# iotaCore-Power.net
KiCad netlist of a schematic drawn in Altium Designer
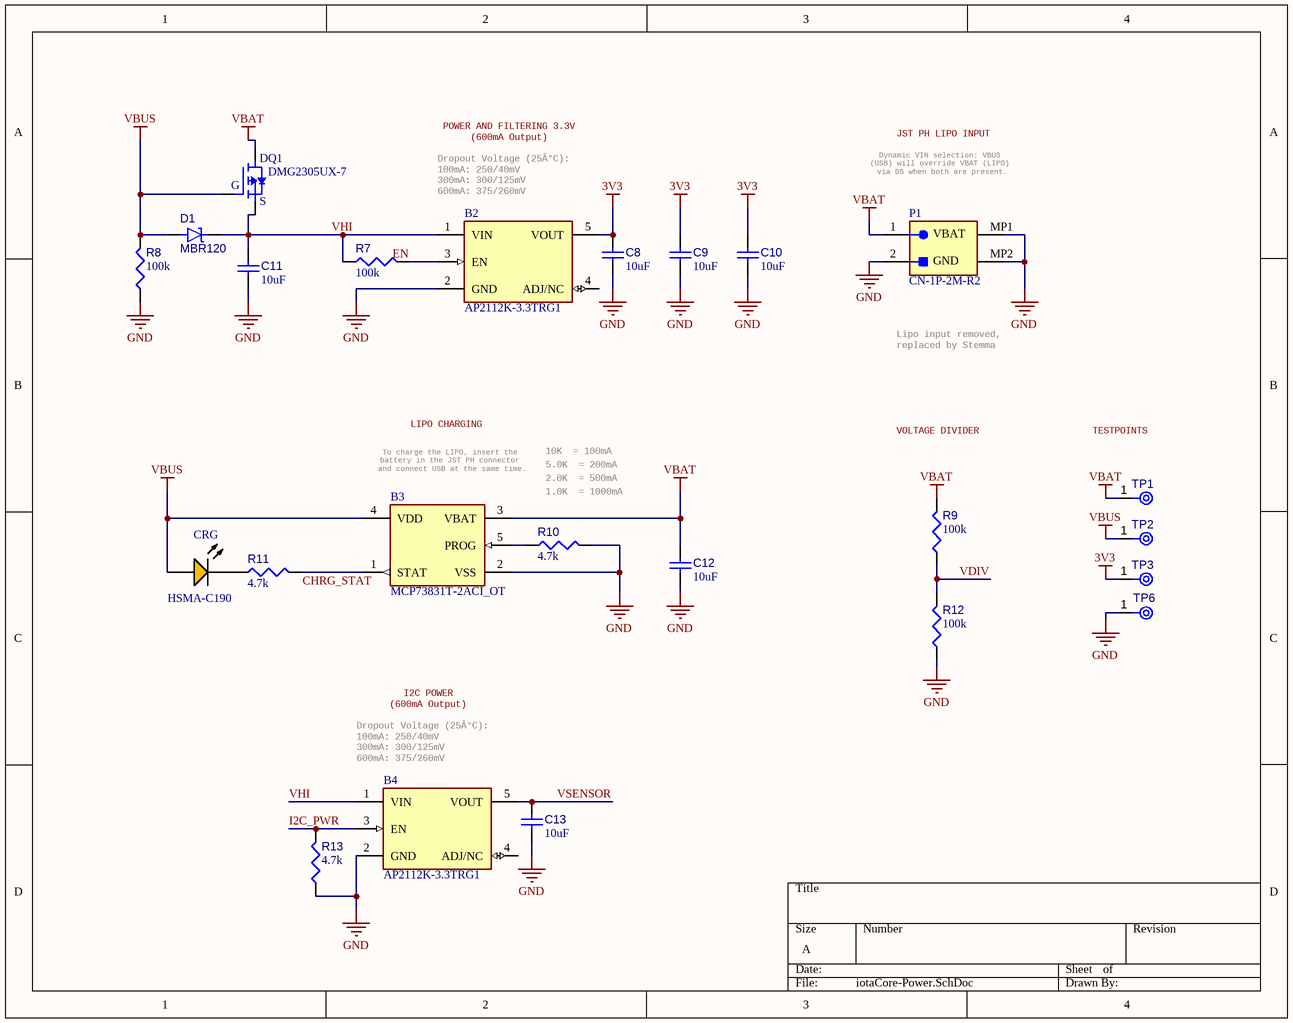
[diagram p0: iotaCore-Power.SchDoc]

(export (version "E")
  (design (tool "Eeschema 10.0.6"))
  (components
    (comp (ref "B2")
      (value "AP2112K-3.3TRG1")
      (footprint "SOT95P270X145-5N")
      (fields (field (name "MOUSER PART NUMBER") "621-AP2112K-3.3TRG1"))
      (libsource (lib "Prototypical Design") (part "AP2112K-3.3TRG1"))
    )
    (comp (ref "B3")
      (value "MCP73831T-2ACI_OT")
      (footprint "SOT95P270X145-5N")
      (description "Li-Ion Charge Controller 4.2V SOT23-5")
      (fields
        (field (name "MOUSER PART NUMBER") "579-MCP73831T-2ACIOT")
        (field (name "MANUFACTURER_PART_NUMBER") "MCP73831T-2ACI/OT")
      )
      (libsource (lib "Prototypical Design") (part "MCP73831T-2ACI_OT"))
    )
    (comp (ref "B4")
      (value "AP2112K-3.3TRG1")
      (footprint "SOT95P270X145-5N")
      (fields (field (name "MOUSER PART NUMBER") "621-AP2112K-3.3TRG1"))
      (libsource (lib "Prototypical Design") (part "AP2112K-3.3TRG1"))
    )
    (comp (ref "C8")
      (value "10uF")
      (footprint "CAPC1608X87X35NL15T15")
      (description "Chip Capacitor, 10 uF, +/- 0.25 uF, 50 V, 0603 (1608 Metric)")
      (fields
        (field (name "TOLERANCE") "0.25%")
        (field (name "Comment") "Capacitor 10 uF +/- 0.25 uF 50 V 0603")
      )
      (libsource (lib "Prototypical Design") (part "CAP-NP-2"))
    )
    (comp (ref "C9")
      (value "10uF")
      (footprint "CAPC1608X87X35NL15T15")
      (description "Chip Capacitor, 10 uF, +/- 0.25 uF, 50 V, 0603 (1608 Metric)")
      (fields
        (field (name "TOLERANCE") "0.25%")
        (field (name "Comment") "Capacitor 10 uF +/- 0.25 uF 50 V 0603")
      )
      (libsource (lib "Prototypical Design") (part "CAP-NP-2"))
    )
    (comp (ref "C10")
      (value "10uF")
      (footprint "CAPC1608X87X35NL15T15")
      (description "Chip Capacitor, 10 uF, +/- 0.25 uF, 50 V, 0603 (1608 Metric)")
      (fields
        (field (name "TOLERANCE") "0.25%")
        (field (name "Comment") "Capacitor 10 uF +/- 0.25 uF 50 V 0603")
      )
      (libsource (lib "Prototypical Design") (part "CAP-NP-2"))
    )
    (comp (ref "C11")
      (value "10uF")
      (footprint "CAPC1608X87X35NL15T15")
      (description "Chip Capacitor, 10 uF, +/- 0.25 uF, 50 V, 0603 (1608 Metric)")
      (fields
        (field (name "TOLERANCE") "0.25%")
        (field (name "Comment") "Capacitor 10 uF +/- 0.25 uF 50 V 0603")
      )
      (libsource (lib "Prototypical Design") (part "CAP-NP-2"))
    )
    (comp (ref "C12")
      (value "10uF")
      (footprint "CAPC1608X87X35NL15T15")
      (description "Chip Capacitor, 10 uF, +/- 0.25 uF, 50 V, 0603 (1608 Metric)")
      (fields
        (field (name "TOLERANCE") "0.25%")
        (field (name "Comment") "Capacitor 10 uF +/- 0.25 uF 50 V 0603")
      )
      (libsource (lib "Prototypical Design") (part "CAP-NP-2"))
    )
    (comp (ref "C13")
      (value "10uF")
      (footprint "CAPC1608X87X35NL15T15")
      (description "Chip Capacitor, 10 uF, +/- 0.25 uF, 50 V, 0603 (1608 Metric)")
      (fields
        (field (name "TOLERANCE") "0.25%")
        (field (name "Comment") "Capacitor 10 uF +/- 0.25 uF 50 V 0603")
      )
      (libsource (lib "Prototypical Design") (part "CAP-NP-2"))
    )
    (comp (ref "CRG")
      (value "HSMA-C190")
      (footprint "AVAG-HSMX-C190_V")
      (description "LED Uni-Color Amber, 60 mW, 20 mA, -40 to 85 degC, 2-Pin SMD, RoHS, Tape and Reel")
      (fields (field (name "POWER") "60mW") (field (name "MANUFACTURER") "Avago"))
      (libsource (lib "Prototypical Design") (part "LED-AMBER-AK-2"))
    )
    (comp (ref "D1")
      (value "MBR120")
      (footprint "ONSC-SOD-123FL-2-498-01_V")
      (description "Diode")
      (libsource (lib "Prototypical Design") (part "MBR120"))
    )
    (comp (ref "P1")
      (value "CN-1P-2M-R2")
      (footprint "JST- S2B-PH-SM4-TB(LF)(SN)-2_V")
      (libsource (lib "Prototypical Design") (part "CN-1P-2M-R2"))
    )
    (comp (ref "Q1")
      (value "DMG2305UX-7")
      (footprint "FP-SOT23-MFG")
      (libsource (lib "Prototypical Design") (part "MOSFET-NPN-3"))
    )
    (comp (ref "R7")
      (value "100k")
      (footprint "RESC1608X55X25ML10T15")
      (description "Chip Resistor, 100 KOhm, +/- 1%, 0.1 W, -55 to 155 degC, 0603 (1608 Metric)")
      (fields (field (name "TOLERANCE") "1%") (field (name "POWER") "100mW"))
      (libsource (lib "Prototypical Design") (part "RES-2"))
    )
    (comp (ref "R8")
      (value "100k")
      (footprint "RESC1608X55X25ML10T15")
      (description "Chip Resistor, 100 KOhm, +/- 1%, 0.1 W, -55 to 155 degC, 0603 (1608 Metric)")
      (fields (field (name "TOLERANCE") "1%") (field (name "POWER") "100mW"))
      (libsource (lib "Prototypical Design") (part "RES-2"))
    )
    (comp (ref "R9")
      (value "100k")
      (footprint "RESC1608X55X25ML10T15")
      (description "Chip Resistor, 100 KOhm, +/- 1%, 0.1 W, -55 to 155 degC, 0603 (1608 Metric)")
      (fields (field (name "TOLERANCE") "1%") (field (name "POWER") "100mW"))
      (libsource (lib "Prototypical Design") (part "RES-2"))
    )
    (comp (ref "R10")
      (value "4.7k")
      (footprint "RESC1608X55X25ML10T15")
      (description "Chip Resistor, 4.7 KOhm, +/- 1%, 0.1 W, -55 to 155 degC, 0603 (1608 Metric)")
      (fields (field (name "TOLERANCE") "1%") (field (name "POWER") "100mW"))
      (libsource (lib "Prototypical Design") (part "RES-2"))
    )
    (comp (ref "R11")
      (value "4.7k")
      (footprint "RESC1608X55X25ML10T15")
      (description "Chip Resistor, 1 KOhm, +/- 1%, 0.1 W, -55 to 155 degC, 0603 (1608 Metric)")
      (fields (field (name "TOLERANCE") "1%") (field (name "POWER") "100mW"))
      (libsource (lib "Prototypical Design") (part "RES-2"))
    )
    (comp (ref "R12")
      (value "100k")
      (footprint "RESC1608X55X25ML10T15")
      (description "Chip Resistor, 100 KOhm, +/- 1%, 0.1 W, -55 to 155 degC, 0603 (1608 Metric)")
      (fields (field (name "TOLERANCE") "1%") (field (name "POWER") "100mW"))
      (libsource (lib "Prototypical Design") (part "RES-2"))
    )
    (comp (ref "R13")
      (value "4.7k")
      (footprint "RESC1608X55X25ML10T15")
      (description "Chip Resistor, 4.7 KOhm, +/- 1%, 0.1 W, -55 to 155 degC, 0603 (1608 Metric)")
      (fields (field (name "TOLERANCE") "1%") (field (name "POWER") "100mW"))
      (libsource (lib "Prototypical Design") (part "RES-2"))
    )
    (comp (ref "TP1")
      (value "TPAD6R")
      (footprint "TP06R")
      (description "0.6mm round")
      (libsource (lib "McIntyre Industries") (part "CMP-001-0001-4"))
    )
    (comp (ref "TP2")
      (value "TPAD6R")
      (footprint "TP06R")
      (description "0.6mm round")
      (libsource (lib "McIntyre Industries") (part "CMP-001-0001-4"))
    )
    (comp (ref "TP3")
      (value "TPAD6R")
      (footprint "TP06R")
      (description "0.6mm round")
      (libsource (lib "McIntyre Industries") (part "CMP-001-0001-4"))
    )
    (comp (ref "TP6")
      (value "TPAD6R")
      (footprint "TP06R")
      (description "0.6mm round")
      (libsource (lib "McIntyre Industries") (part "CMP-001-0001-4"))
    )
  )
  (nets
    (net (code "1") (name "/CHRG_STAT") (class "Default")
      (node (ref "B3") (pin "1") (pinfunction "STAT_1") (pintype "output"))
      (node (ref "R11") (pin "2") (pinfunction "2_2") (pintype "passive"))
    )
    (net (code "2") (name "/EN") (class "Default")
      (node (ref "B2") (pin "3") (pinfunction "EN_3") (pintype "input"))
      (node (ref "R7") (pin "2") (pinfunction "2_2") (pintype "passive"))
    )
    (net (code "3") (name "/I2C_PWR") (class "Default")
      (node (ref "B4") (pin "3") (pinfunction "EN_3") (pintype "input"))
      (node (ref "R13") (pin "2") (pinfunction "2_2") (pintype "passive"))
    )
    (net (code "4") (name "/VDIV") (class "Default")
      (node (ref "R12") (pin "2") (pinfunction "2_2") (pintype "passive"))
      (node (ref "R9") (pin "1") (pinfunction "1_1") (pintype "passive"))
    )
    (net (code "5") (name "/VHI") (class "Default")
      (node (ref "B2") (pin "1") (pinfunction "VIN_1") (pintype "passive"))
      (node (ref "B4") (pin "1") (pinfunction "VIN_1") (pintype "passive"))
      (node (ref "C11") (pin "2") (pinfunction "2_2") (pintype "passive"))
      (node (ref "D1") (pin "1") (pinfunction "K_1") (pintype "passive"))
      (node (ref "Q1") (pin "2") (pinfunction "S_2") (pintype "passive"))
      (node (ref "R7") (pin "1") (pinfunction "1_1") (pintype "passive"))
    )
    (net (code "6") (name "/VSENSOR") (class "Default")
      (node (ref "B4") (pin "5") (pinfunction "VOUT_5") (pintype "passive"))
      (node (ref "C13") (pin "2") (pinfunction "2_2") (pintype "passive"))
    )
    (net (code "7") (name "3V3") (class "Default")
      (node (ref "B2") (pin "5") (pinfunction "VOUT_5") (pintype "passive"))
      (node (ref "C10") (pin "2") (pinfunction "2_2") (pintype "passive"))
      (node (ref "C8") (pin "2") (pinfunction "2_2") (pintype "passive"))
      (node (ref "C9") (pin "2") (pinfunction "2_2") (pintype "passive"))
      (node (ref "TP3") (pin "1") (pinfunction "TP_1") (pintype "passive"))
    )
    (net (code "8") (name "GND") (class "Default")
      (node (ref "B2") (pin "2") (pinfunction "GND_2") (pintype "passive"))
      (node (ref "B3") (pin "2") (pinfunction "VSS_2") (pintype "passive"))
      (node (ref "B4") (pin "2") (pinfunction "GND_2") (pintype "passive"))
      (node (ref "C10") (pin "1") (pinfunction "1_1") (pintype "passive"))
      (node (ref "C11") (pin "1") (pinfunction "1_1") (pintype "passive"))
      (node (ref "C12") (pin "1") (pinfunction "1_1") (pintype "passive"))
      (node (ref "C13") (pin "1") (pinfunction "1_1") (pintype "passive"))
      (node (ref "C8") (pin "1") (pinfunction "1_1") (pintype "passive"))
      (node (ref "C9") (pin "1") (pinfunction "1_1") (pintype "passive"))
      (node (ref "P1") (pin "2") (pinfunction "2_2") (pintype "passive"))
      (node (ref "P1") (pin "MP1") (pinfunction "MP1_MP1") (pintype "passive"))
      (node (ref "P1") (pin "MP2") (pinfunction "MP2_MP2") (pintype "passive"))
      (node (ref "R10") (pin "2") (pinfunction "2_2") (pintype "passive"))
      (node (ref "R12") (pin "1") (pinfunction "1_1") (pintype "passive"))
      (node (ref "R13") (pin "1") (pinfunction "1_1") (pintype "passive"))
      (node (ref "R8") (pin "1") (pinfunction "1_1") (pintype "passive"))
      (node (ref "TP6") (pin "1") (pinfunction "TP_1") (pintype "passive"))
    )
    (net (code "9") (name "Net-(B3-PROG)") (class "Default")
      (node (ref "B3") (pin "5") (pinfunction "PROG_5") (pintype "input"))
      (node (ref "R10") (pin "1") (pinfunction "1_1") (pintype "passive"))
    )
    (net (code "10") (name "Net-(CRG-K)") (class "Default")
      (node (ref "CRG") (pin "2") (pinfunction "K_2") (pintype "passive"))
      (node (ref "R11") (pin "1") (pinfunction "1_1") (pintype "passive"))
    )
    (net (code "11") (name "VBAT") (class "Default")
      (node (ref "B3") (pin "3") (pinfunction "VBAT_3") (pintype "passive"))
      (node (ref "C12") (pin "2") (pinfunction "2_2") (pintype "passive"))
      (node (ref "P1") (pin "1") (pinfunction "1_1") (pintype "passive"))
      (node (ref "Q1") (pin "3") (pinfunction "D_3") (pintype "passive"))
      (node (ref "R9") (pin "2") (pinfunction "2_2") (pintype "passive"))
      (node (ref "TP1") (pin "1") (pinfunction "TP_1") (pintype "passive"))
    )
    (net (code "12") (name "VBUS") (class "Default")
      (node (ref "B3") (pin "4") (pinfunction "VDD_4") (pintype "passive"))
      (node (ref "CRG") (pin "1") (pinfunction "A_1") (pintype "passive"))
      (node (ref "D1") (pin "2") (pinfunction "A_2") (pintype "passive"))
      (node (ref "Q1") (pin "1") (pinfunction "G_1") (pintype "passive"))
      (node (ref "R8") (pin "2") (pinfunction "2_2") (pintype "passive"))
      (node (ref "TP2") (pin "1") (pinfunction "TP_1") (pintype "passive"))
    )
    (net (code "13") (name "unconnected-(B2-ADJ{slash}NC-Pad4)") (class "Default")
      (node (ref "B2") (pin "4") (pinfunction "ADJ/NC_4") (pintype "bidirectional"))
    )
    (net (code "14") (name "unconnected-(B4-ADJ{slash}NC-Pad4)") (class "Default")
      (node (ref "B4") (pin "4") (pinfunction "ADJ/NC_4") (pintype "bidirectional"))
    )
  )
)
